# MKR485ShieldV3_0.net
KiCad netlist of a schematic drawn in EAGLE
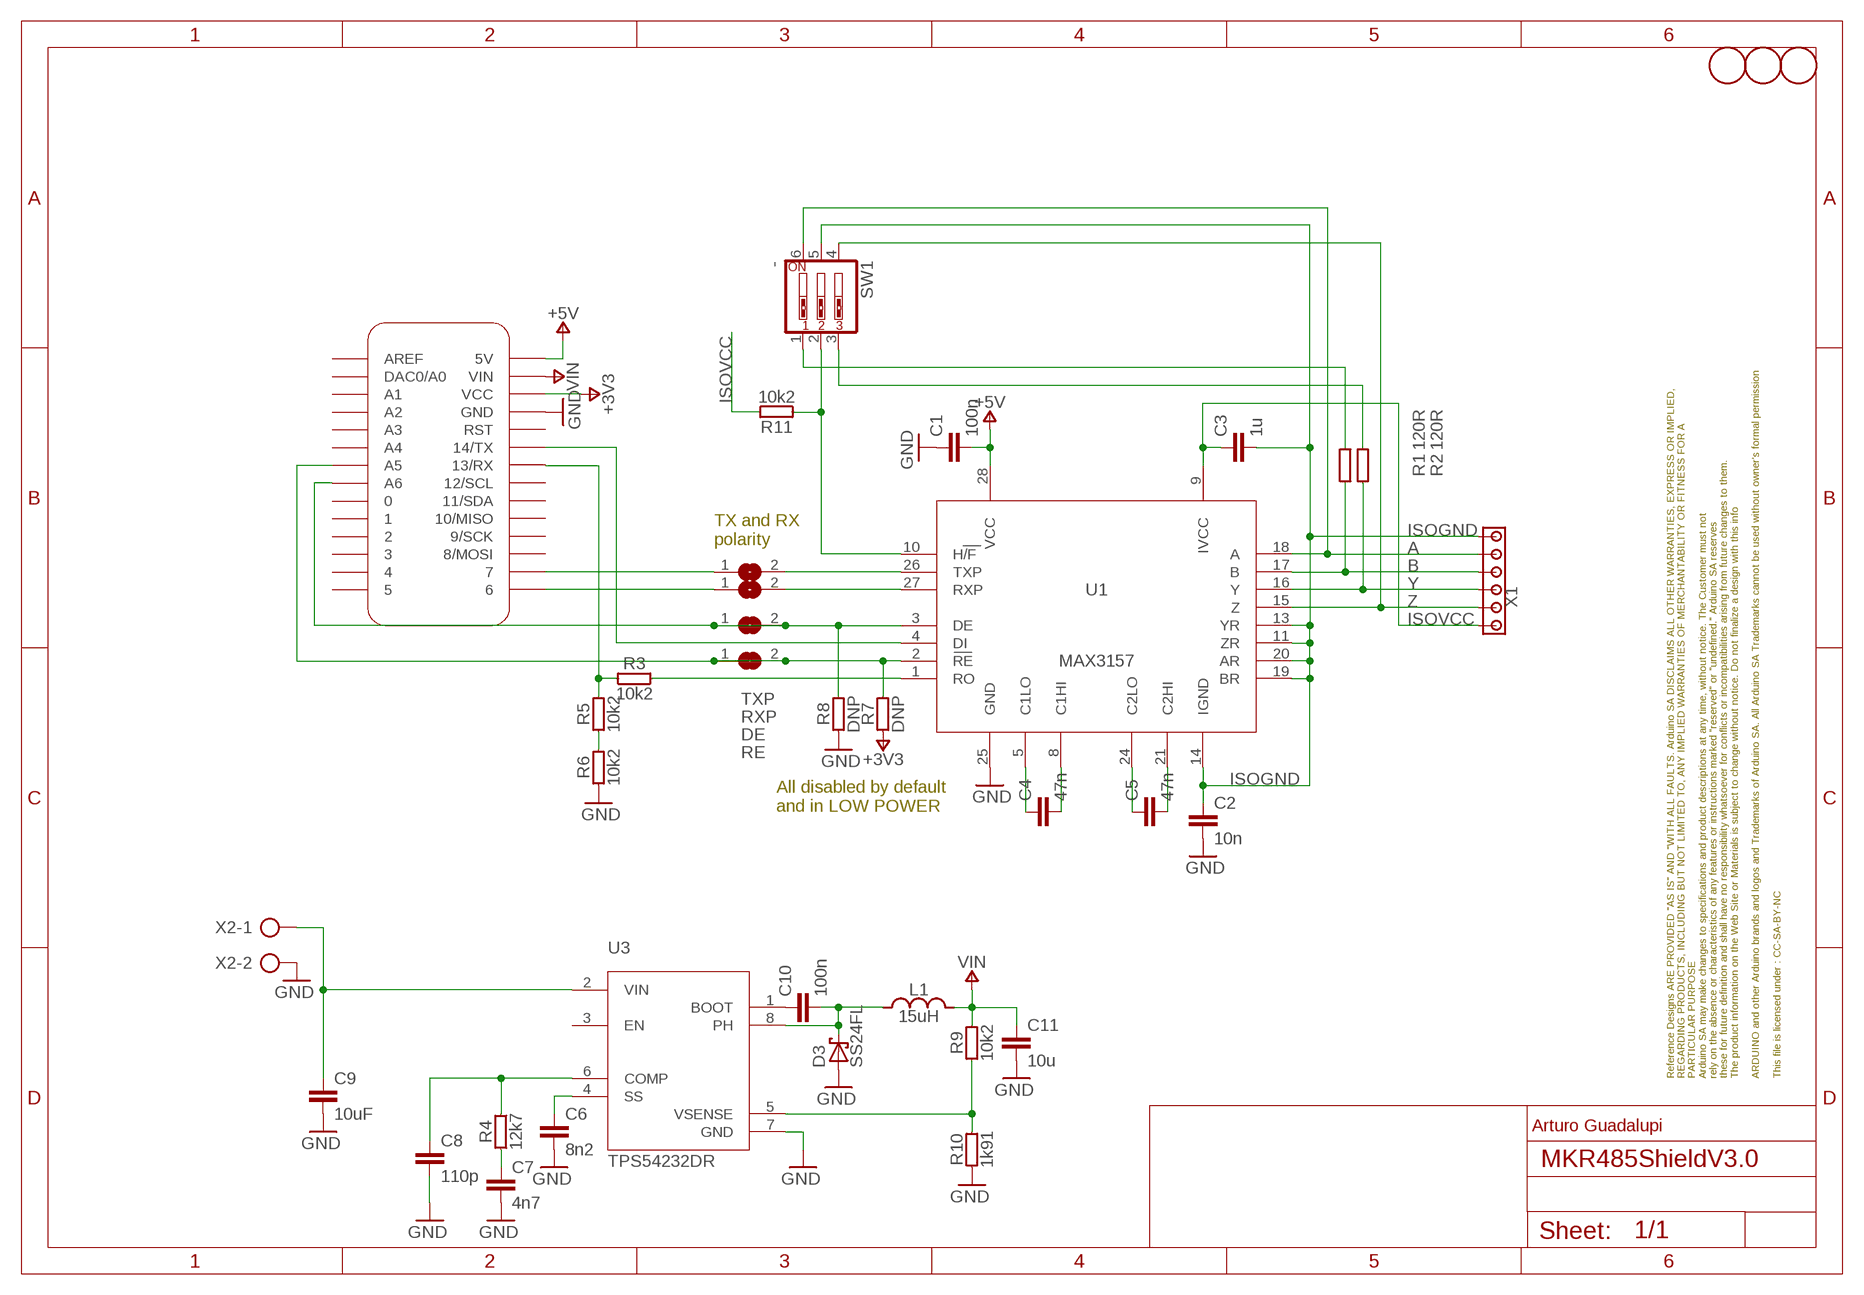
[diagram p0: schematic, sheet 1]

(export (version "E")
  (design (tool "Eeschema 10.0.6"))
  (components
    (comp (ref "C1")
      (value "100n")
      (footprint "eagle-import:0402-1005X55N")
      (fields (field (name "MANUFACTURER") "TDK"))
      (libsource (lib "eagle-import") (part "C-0402-100NF"))
    )
    (comp (ref "C2")
      (value "10n")
      (footprint "eagle-import:0603-1608X90N")
      (fields (field (name "MANUFACTURER") "Murata"))
      (libsource (lib "eagle-import") (part "C-0603-10NF"))
    )
    (comp (ref "C3")
      (value "1u")
      (footprint "eagle-import:0603-1608X90N")
      (fields (field (name "MANUFACTURER") "Samsung"))
      (libsource (lib "eagle-import") (part "C-0603-1UF"))
    )
    (comp (ref "C4")
      (value "47n")
      (footprint "eagle-import:0402-1005X55N")
      (fields (field (name "MANUFACTURER") "Murata"))
      (libsource (lib "eagle-import") (part "C-0402-47N"))
    )
    (comp (ref "C5")
      (value "47n")
      (footprint "eagle-import:0402-1005X55N")
      (fields (field (name "MANUFACTURER") "Murata"))
      (libsource (lib "eagle-import") (part "C-0402-47N"))
    )
    (comp (ref "C6")
      (value "8n2")
      (footprint "eagle-import:0402-1005X55N")
      (fields (field (name "MANUFACTURER") "Yageo"))
      (libsource (lib "eagle-import") (part "C-0402-8N2"))
    )
    (comp (ref "C7")
      (value "4n7")
      (footprint "eagle-import:0402-1005X55N")
      (fields (field (name "MANUFACTURER") "Murata"))
      (libsource (lib "eagle-import") (part "C-0402-4N7"))
    )
    (comp (ref "C8")
      (value "110p")
      (footprint "eagle-import:0402-1005X55N")
      (fields (field (name "MANUFACTURER") "Murata"))
      (libsource (lib "eagle-import") (part "C-0402-110P"))
    )
    (comp (ref "C9")
      (value "10uF")
      (footprint "eagle-import:C1206")
      (fields (field (name "MANUFACTURER") "TDK Corporation"))
      (libsource (lib "eagle-import") (part "C-1206-10UF"))
    )
    (comp (ref "C10")
      (value "100n")
      (footprint "eagle-import:0402-1005X55N")
      (fields (field (name "MANUFACTURER") "TDK"))
      (libsource (lib "eagle-import") (part "C-0402-100NF"))
    )
    (comp (ref "C11")
      (value "10u")
      (footprint "eagle-import:0603-1608X90N")
      (fields (field (name "MANUFACTURER") "Murata"))
      (libsource (lib "eagle-import") (part "C-0603-10UF"))
    )
    (comp (ref "D3")
      (value "SS24FL")
      (footprint "eagle-import:SOD123F")
      (fields (field (name "MANUFACTURER") "Fairchild"))
      (libsource (lib "eagle-import") (part "SS24FL"))
    )
    (comp (ref "DE") (value "DNP") (footprint "eagle-import:SJ") (libsource (lib "eagle-import") (part "SJ")))
    (comp (ref "FD1")
      (value "DNP")
      (footprint "eagle-import:FD-1-1.5")
      (libsource (lib "eagle-import") (part "FIDUCIAL-1.5MM"))
    )
    (comp (ref "FD2")
      (value "DNP")
      (footprint "eagle-import:FD-1-1.5")
      (libsource (lib "eagle-import") (part "FIDUCIAL-1.5MM"))
    )
    (comp (ref "FD3")
      (value "DNP")
      (footprint "eagle-import:FD-1-1.5")
      (libsource (lib "eagle-import") (part "FIDUCIAL-1.5MM"))
    )
    (comp (ref "FRAME1")
      (value "DNP")
      (footprint "eagle-import:FRAME")
      (libsource (lib "eagle-import") (part "A4L-LOC"))
    )
    (comp (ref "L1")
      (value "15uH")
      (footprint "eagle-import:SRN6045")
      (fields (field (name "MANUFACTURER") "Bourns"))
      (libsource (lib "eagle-import") (part "LSRN"))
    )
    (comp (ref "MKR1")
      (value "DNP")
      (footprint "eagle-import:MKRBOARD-DIM")
      (libsource (lib "eagle-import") (part "MKRBOARD-DIM-DNP"))
    )
    (comp (ref "R1")
      (value "120R")
      (footprint "eagle-import:0402-1005X55N")
      (fields (field (name "MANUFACTURER") "Yageo"))
      (libsource (lib "eagle-import") (part "R-0402-120R"))
    )
    (comp (ref "R2")
      (value "120R")
      (footprint "eagle-import:0402-1005X55N")
      (fields (field (name "MANUFACTURER") "Yageo"))
      (libsource (lib "eagle-import") (part "R-0402-120R"))
    )
    (comp (ref "R3")
      (value "10k2")
      (footprint "eagle-import:0402-1005X55N")
      (fields (field (name "MANUFACTURER") "Yageo"))
      (libsource (lib "eagle-import") (part "R-0402-10K2"))
    )
    (comp (ref "R4")
      (value "12k7")
      (footprint "eagle-import:0402-1005X55N")
      (fields (field (name "MANUFACTURER") "Yageo"))
      (libsource (lib "eagle-import") (part "R-0402-12K7"))
    )
    (comp (ref "R5")
      (value "10k2")
      (footprint "eagle-import:0402-1005X55N")
      (fields (field (name "MANUFACTURER") "Yageo"))
      (libsource (lib "eagle-import") (part "R-0402-10K2"))
    )
    (comp (ref "R6")
      (value "10k2")
      (footprint "eagle-import:0402-1005X55N")
      (fields (field (name "MANUFACTURER") "Yageo"))
      (libsource (lib "eagle-import") (part "R-0402-10K2"))
    )
    (comp (ref "R7")
      (value "DNP")
      (footprint "eagle-import:0402-1005X55N")
      (libsource (lib "eagle-import") (part "R-0402-DNP"))
    )
    (comp (ref "R8")
      (value "DNP")
      (footprint "eagle-import:0402-1005X55N")
      (libsource (lib "eagle-import") (part "R-0402-DNP"))
    )
    (comp (ref "R9")
      (value "10k2")
      (footprint "eagle-import:0402-1005X55N")
      (fields (field (name "MANUFACTURER") "Yageo"))
      (libsource (lib "eagle-import") (part "R-0402-10K2"))
    )
    (comp (ref "R10")
      (value "1k91")
      (footprint "eagle-import:0402-1005X55N")
      (fields (field (name "MANUFACTURER") "Yageo"))
      (libsource (lib "eagle-import") (part "R-0402-1K91"))
    )
    (comp (ref "R11")
      (value "10k2")
      (footprint "eagle-import:0402-1005X55N")
      (fields (field (name "MANUFACTURER") "Yageo"))
      (libsource (lib "eagle-import") (part "R-0402-10K2"))
    )
    (comp (ref "RE") (value "DNP") (footprint "eagle-import:SJ") (libsource (lib "eagle-import") (part "SJ")))
    (comp (ref "RXP")
      (value "DNP")
      (footprint "eagle-import:SJ")
      (libsource (lib "eagle-import") (part "SJ"))
    )
    (comp (ref "SW1")
      (value "-")
      (footprint "eagle-import:EDG-03")
      (fields (field (name "MANUFACTURER") "CTS"))
      (libsource (lib "eagle-import") (part "SW_DIP-3"))
    )
    (comp (ref "TXP")
      (value "DNP")
      (footprint "eagle-import:SJ")
      (libsource (lib "eagle-import") (part "SJ"))
    )
    (comp (ref "U1")
      (value "MAX3157")
      (footprint "eagle-import:TSSOP28")
      (fields (field (name "MANUFACTURER") "Maxim"))
      (libsource (lib "eagle-import") (part "MAX3157"))
    )
    (comp (ref "U3")
      (value "TPS54232DR")
      (footprint "eagle-import:SO08")
      (fields (field (name "MANUFACTURER") "Texas Instruments"))
      (libsource (lib "eagle-import") (part "TPS54232"))
    )
    (comp (ref "X1")
      (value "-")
      (footprint "eagle-import:SCREW6X2.54")
      (fields (field (name "MANUFACTURER") "Phoenix"))
      (libsource (lib "eagle-import") (part "SCREW6X2.54"))
    )
    (comp (ref "X2")
      (value "-")
      (footprint "eagle-import:AK300_2")
      (fields (field (name "MANUFACTURER") "On Shore"))
      (libsource (lib "eagle-import") (part "AK300/2"))
    )
  )
  (nets
    (net (code "1") (name "+3V3") (class "Default")
      (node (ref "MKR1") (pin "VCC") (pinfunction "VCC_VCC") (pintype "bidirectional"))
      (node (ref "R7") (pin "1") (pinfunction "1_1") (pintype "passive"))
    )
    (net (code "2") (name "+5V") (class "Default")
      (node (ref "C1") (pin "2") (pinfunction "2_2") (pintype "passive"))
      (node (ref "MKR1") (pin "5V") (pinfunction "5V_5V") (pintype "bidirectional"))
      (node (ref "U1") (pin "28") (pinfunction "VCC_28") (pintype "bidirectional"))
    )
    (net (code "3") (name "/A") (class "Default")
      (node (ref "SW1") (pin "6") (pinfunction "6_6") (pintype "passive"))
      (node (ref "U1") (pin "18") (pinfunction "A_18") (pintype "bidirectional"))
      (node (ref "X1") (pin "5") (pinfunction "5_5") (pintype "passive"))
    )
    (net (code "4") (name "/B") (class "Default")
      (node (ref "R1") (pin "1") (pinfunction "1_1") (pintype "passive"))
      (node (ref "U1") (pin "17") (pinfunction "B_17") (pintype "bidirectional"))
      (node (ref "X1") (pin "4") (pinfunction "4_4") (pintype "passive"))
    )
    (net (code "5") (name "/ISOGND") (class "Default")
      (node (ref "C2") (pin "1") (pinfunction "1_1") (pintype "passive"))
      (node (ref "C3") (pin "2") (pinfunction "2_2") (pintype "passive"))
      (node (ref "SW1") (pin "5") (pinfunction "5_5") (pintype "passive"))
      (node (ref "U1") (pin "11") (pinfunction "ZR_11") (pintype "bidirectional"))
      (node (ref "U1") (pin "13") (pinfunction "YR_13") (pintype "bidirectional"))
      (node (ref "U1") (pin "14") (pinfunction "IGND_14") (pintype "bidirectional"))
      (node (ref "U1") (pin "19") (pinfunction "BR_19") (pintype "bidirectional"))
      (node (ref "U1") (pin "20") (pinfunction "AR_20") (pintype "bidirectional"))
      (node (ref "X1") (pin "6") (pinfunction "6_6") (pintype "passive"))
    )
    (net (code "6") (name "/ISOVCC") (class "Default")
      (node (ref "C3") (pin "1") (pinfunction "1_1") (pintype "passive"))
      (node (ref "R11") (pin "2") (pinfunction "2_2") (pintype "passive"))
      (node (ref "U1") (pin "9") (pinfunction "IVCC_9") (pintype "bidirectional"))
      (node (ref "X1") (pin "1") (pinfunction "1_1") (pintype "passive"))
    )
    (net (code "7") (name "/Y") (class "Default")
      (node (ref "R2") (pin "1") (pinfunction "1_1") (pintype "passive"))
      (node (ref "U1") (pin "16") (pinfunction "Y_16") (pintype "bidirectional"))
      (node (ref "X1") (pin "3") (pinfunction "3_3") (pintype "passive"))
    )
    (net (code "8") (name "/Z") (class "Default")
      (node (ref "SW1") (pin "4") (pinfunction "4_4") (pintype "passive"))
      (node (ref "U1") (pin "15") (pinfunction "Z_15") (pintype "bidirectional"))
      (node (ref "X1") (pin "2") (pinfunction "2_2") (pintype "passive"))
    )
    (net (code "9") (name "GND") (class "Default")
      (node (ref "C1") (pin "1") (pinfunction "1_1") (pintype "passive"))
      (node (ref "C11") (pin "2") (pinfunction "2_2") (pintype "passive"))
      (node (ref "C2") (pin "2") (pinfunction "2_2") (pintype "passive"))
      (node (ref "C6") (pin "2") (pinfunction "2_2") (pintype "passive"))
      (node (ref "C7") (pin "2") (pinfunction "2_2") (pintype "passive"))
      (node (ref "C8") (pin "2") (pinfunction "2_2") (pintype "passive"))
      (node (ref "C9") (pin "2") (pinfunction "2_2") (pintype "passive"))
      (node (ref "D3") (pin "A") (pinfunction "A_A") (pintype "passive"))
      (node (ref "MKR1") (pin "GND") (pinfunction "GND_GND") (pintype "bidirectional"))
      (node (ref "R10") (pin "1") (pinfunction "1_1") (pintype "passive"))
      (node (ref "R6") (pin "1") (pinfunction "1_1") (pintype "passive"))
      (node (ref "R8") (pin "1") (pinfunction "1_1") (pintype "passive"))
      (node (ref "U1") (pin "25") (pinfunction "GND_25") (pintype "bidirectional"))
      (node (ref "U3") (pin "7") (pinfunction "GND_7") (pintype "bidirectional"))
      (node (ref "X2") (pin "2") (pinfunction "KL_2") (pintype "passive"))
    )
    (net (code "10") (name "Net-(C7-Pad1)") (class "Default")
      (node (ref "C7") (pin "1") (pinfunction "1_1") (pintype "passive"))
      (node (ref "R4") (pin "1") (pinfunction "1_1") (pintype "passive"))
    )
    (net (code "11") (name "Net-(MKR1-13{slash}RX)") (class "Default")
      (node (ref "MKR1") (pin "13") (pinfunction "13/RX_13") (pintype "bidirectional"))
      (node (ref "R3") (pin "1") (pinfunction "1_1") (pintype "passive"))
      (node (ref "R5") (pin "2") (pinfunction "2_2") (pintype "passive"))
    )
    (net (code "12") (name "Net-(MKR1-14{slash}TX)") (class "Default")
      (node (ref "MKR1") (pin "14") (pinfunction "14/TX_14") (pintype "bidirectional"))
      (node (ref "U1") (pin "4") (pinfunction "DI_4") (pintype "bidirectional"))
    )
    (net (code "13") (name "Net-(MKR1-Pad6)") (class "Default")
      (node (ref "MKR1") (pin "6") (pinfunction "6_6") (pintype "bidirectional"))
      (node (ref "RXP") (pin "1") (pinfunction "1_1") (pintype "passive"))
    )
    (net (code "14") (name "Net-(MKR1-Pad7)") (class "Default")
      (node (ref "MKR1") (pin "7") (pinfunction "7_7") (pintype "bidirectional"))
      (node (ref "TXP") (pin "1") (pinfunction "1_1") (pintype "passive"))
    )
    (net (code "15") (name "Net-(R1-Pad2)") (class "Default")
      (node (ref "R1") (pin "2") (pinfunction "2_2") (pintype "passive"))
      (node (ref "SW1") (pin "1") (pinfunction "1_1") (pintype "passive"))
    )
    (net (code "16") (name "Net-(R2-Pad2)") (class "Default")
      (node (ref "R2") (pin "2") (pinfunction "2_2") (pintype "passive"))
      (node (ref "SW1") (pin "3") (pinfunction "3_3") (pintype "passive"))
    )
    (net (code "17") (name "Net-(R5-Pad1)") (class "Default")
      (node (ref "R5") (pin "1") (pinfunction "1_1") (pintype "passive"))
      (node (ref "R6") (pin "2") (pinfunction "2_2") (pintype "passive"))
    )
    (net (code "18") (name "Net-(U1-C1HI)") (class "Default")
      (node (ref "C4") (pin "2") (pinfunction "2_2") (pintype "passive"))
      (node (ref "U1") (pin "8") (pinfunction "C1HI_8") (pintype "bidirectional"))
    )
    (net (code "19") (name "Net-(U1-C1LO)") (class "Default")
      (node (ref "C4") (pin "1") (pinfunction "1_1") (pintype "passive"))
      (node (ref "U1") (pin "5") (pinfunction "C1LO_5") (pintype "bidirectional"))
    )
    (net (code "20") (name "Net-(U1-C2HI)") (class "Default")
      (node (ref "C5") (pin "2") (pinfunction "2_2") (pintype "passive"))
      (node (ref "U1") (pin "21") (pinfunction "C2HI_21") (pintype "bidirectional"))
    )
    (net (code "21") (name "Net-(U1-C2LO)") (class "Default")
      (node (ref "C5") (pin "1") (pinfunction "1_1") (pintype "passive"))
      (node (ref "U1") (pin "24") (pinfunction "C2LO_24") (pintype "bidirectional"))
    )
    (net (code "22") (name "Net-(U1-DE)") (class "Default")
      (node (ref "DE") (pin "1") (pinfunction "1_1") (pintype "passive"))
      (node (ref "DE") (pin "2") (pinfunction "2_2") (pintype "passive"))
      (node (ref "MKR1") (pin "A6") (pinfunction "A6_A6") (pintype "bidirectional"))
      (node (ref "R8") (pin "2") (pinfunction "2_2") (pintype "passive"))
      (node (ref "U1") (pin "3") (pinfunction "DE_3") (pintype "bidirectional"))
    )
    (net (code "23") (name "Net-(U1-H{slash}F)") (class "Default")
      (node (ref "R11") (pin "1") (pinfunction "1_1") (pintype "passive"))
      (node (ref "SW1") (pin "2") (pinfunction "2_2") (pintype "passive"))
      (node (ref "U1") (pin "10") (pinfunction "H/F_10") (pintype "bidirectional"))
    )
    (net (code "24") (name "Net-(U1-RE)") (class "Default")
      (node (ref "MKR1") (pin "A5") (pinfunction "A5_A5") (pintype "bidirectional"))
      (node (ref "R7") (pin "2") (pinfunction "2_2") (pintype "passive"))
      (node (ref "RE") (pin "1") (pinfunction "1_1") (pintype "passive"))
      (node (ref "RE") (pin "2") (pinfunction "2_2") (pintype "passive"))
      (node (ref "U1") (pin "2") (pinfunction "RE_2") (pintype "bidirectional"))
    )
    (net (code "25") (name "Net-(U1-RO)") (class "Default")
      (node (ref "R3") (pin "2") (pinfunction "2_2") (pintype "passive"))
      (node (ref "U1") (pin "1") (pinfunction "RO_1") (pintype "bidirectional"))
    )
    (net (code "26") (name "Net-(U1-RXP)") (class "Default")
      (node (ref "RXP") (pin "2") (pinfunction "2_2") (pintype "passive"))
      (node (ref "U1") (pin "27") (pinfunction "RXP_27") (pintype "bidirectional"))
    )
    (net (code "27") (name "Net-(U1-TXP)") (class "Default")
      (node (ref "TXP") (pin "2") (pinfunction "2_2") (pintype "passive"))
      (node (ref "U1") (pin "26") (pinfunction "TXP_26") (pintype "bidirectional"))
    )
    (net (code "28") (name "Net-(U3-BOOT)") (class "Default")
      (node (ref "C10") (pin "1") (pinfunction "1_1") (pintype "passive"))
      (node (ref "U3") (pin "1") (pinfunction "BOOT_1") (pintype "bidirectional"))
    )
    (net (code "29") (name "Net-(U3-COMP)") (class "Default")
      (node (ref "C8") (pin "1") (pinfunction "1_1") (pintype "passive"))
      (node (ref "R4") (pin "2") (pinfunction "2_2") (pintype "passive"))
      (node (ref "U3") (pin "6") (pinfunction "COMP_6") (pintype "bidirectional"))
    )
    (net (code "30") (name "Net-(U3-PH)") (class "Default")
      (node (ref "C10") (pin "2") (pinfunction "2_2") (pintype "passive"))
      (node (ref "D3") (pin "C") (pinfunction "C_C") (pintype "passive"))
      (node (ref "L1") (pin "1") (pinfunction "1_1") (pintype "passive"))
      (node (ref "U3") (pin "8") (pinfunction "PH_8") (pintype "bidirectional"))
    )
    (net (code "31") (name "Net-(U3-SS)") (class "Default")
      (node (ref "C6") (pin "1") (pinfunction "1_1") (pintype "passive"))
      (node (ref "U3") (pin "4") (pinfunction "SS_4") (pintype "bidirectional"))
    )
    (net (code "32") (name "Net-(U3-VIN)") (class "Default")
      (node (ref "C9") (pin "1") (pinfunction "1_1") (pintype "passive"))
      (node (ref "U3") (pin "2") (pinfunction "VIN_2") (pintype "bidirectional"))
      (node (ref "X2") (pin "1") (pinfunction "KL_1") (pintype "passive"))
    )
    (net (code "33") (name "Net-(U3-VSENSE)") (class "Default")
      (node (ref "R10") (pin "2") (pinfunction "2_2") (pintype "passive"))
      (node (ref "R9") (pin "1") (pinfunction "1_1") (pintype "passive"))
      (node (ref "U3") (pin "5") (pinfunction "VSENSE_5") (pintype "bidirectional"))
    )
    (net (code "34") (name "VIN") (class "Default")
      (node (ref "C11") (pin "1") (pinfunction "1_1") (pintype "passive"))
      (node (ref "L1") (pin "2") (pinfunction "2_2") (pintype "passive"))
      (node (ref "MKR1") (pin "VIN") (pinfunction "VIN_VIN") (pintype "bidirectional"))
      (node (ref "R9") (pin "2") (pinfunction "2_2") (pintype "passive"))
    )
    (net (code "35") (name "unconnected-(MKR1-8{slash}MOSI-Pad8)") (class "Default")
      (node (ref "MKR1") (pin "8") (pinfunction "8/MOSI_8") (pintype "bidirectional"))
    )
    (net (code "36") (name "unconnected-(MKR1-9{slash}SCK-Pad9)") (class "Default")
      (node (ref "MKR1") (pin "9") (pinfunction "9/SCK_9") (pintype "bidirectional"))
    )
    (net (code "37") (name "unconnected-(MKR1-10{slash}MISO-Pad10)") (class "Default")
      (node (ref "MKR1") (pin "10") (pinfunction "10/MISO_10") (pintype "bidirectional"))
    )
    (net (code "38") (name "unconnected-(MKR1-11{slash}SDA-Pad11)") (class "Default")
      (node (ref "MKR1") (pin "11") (pinfunction "11/SDA_11") (pintype "bidirectional"))
    )
    (net (code "39") (name "unconnected-(MKR1-12{slash}SCL-Pad12)") (class "Default")
      (node (ref "MKR1") (pin "12") (pinfunction "12/SCL_12") (pintype "bidirectional"))
    )
    (net (code "40") (name "unconnected-(MKR1-DAC0{slash}A0-PadA0)") (class "Default")
      (node (ref "MKR1") (pin "A0") (pinfunction "DAC0/A0_A0") (pintype "bidirectional"))
    )
    (net (code "41") (name "unconnected-(MKR1-Pad0)") (class "Default")
      (node (ref "MKR1") (pin "0") (pinfunction "0_0") (pintype "bidirectional"))
    )
    (net (code "42") (name "unconnected-(MKR1-Pad1)") (class "Default")
      (node (ref "MKR1") (pin "1") (pinfunction "1_1") (pintype "bidirectional"))
    )
    (net (code "43") (name "unconnected-(MKR1-Pad2)") (class "Default")
      (node (ref "MKR1") (pin "2") (pinfunction "2_2") (pintype "bidirectional"))
    )
    (net (code "44") (name "unconnected-(MKR1-Pad3)") (class "Default")
      (node (ref "MKR1") (pin "3") (pinfunction "3_3") (pintype "bidirectional"))
    )
    (net (code "45") (name "unconnected-(MKR1-Pad4)") (class "Default")
      (node (ref "MKR1") (pin "4") (pinfunction "4_4") (pintype "bidirectional"))
    )
    (net (code "46") (name "unconnected-(MKR1-Pad5)") (class "Default")
      (node (ref "MKR1") (pin "5") (pinfunction "5_5") (pintype "bidirectional"))
    )
    (net (code "47") (name "unconnected-(MKR1-PadA1)") (class "Default")
      (node (ref "MKR1") (pin "A1") (pinfunction "A1_A1") (pintype "bidirectional"))
    )
    (net (code "48") (name "unconnected-(MKR1-PadA2)") (class "Default")
      (node (ref "MKR1") (pin "A2") (pinfunction "A2_A2") (pintype "bidirectional"))
    )
    (net (code "49") (name "unconnected-(MKR1-PadA3)") (class "Default")
      (node (ref "MKR1") (pin "A3") (pinfunction "A3_A3") (pintype "bidirectional"))
    )
    (net (code "50") (name "unconnected-(MKR1-PadA4)") (class "Default")
      (node (ref "MKR1") (pin "A4") (pinfunction "A4_A4") (pintype "bidirectional"))
    )
    (net (code "51") (name "unconnected-(MKR1-PadAREF)") (class "Default")
      (node (ref "MKR1") (pin "AREF") (pinfunction "AREF_AREF") (pintype "bidirectional"))
    )
    (net (code "52") (name "unconnected-(MKR1-PadRST)") (class "Default")
      (node (ref "MKR1") (pin "RST") (pinfunction "RST_RST") (pintype "bidirectional"))
    )
    (net (code "53") (name "unconnected-(U3-EN-Pad3)") (class "Default")
      (node (ref "U3") (pin "3") (pinfunction "EN_3") (pintype "bidirectional"))
    )
  )
)
